# 1_cpu_mmu.net
KiCad netlist of a schematic drawn in EAGLE
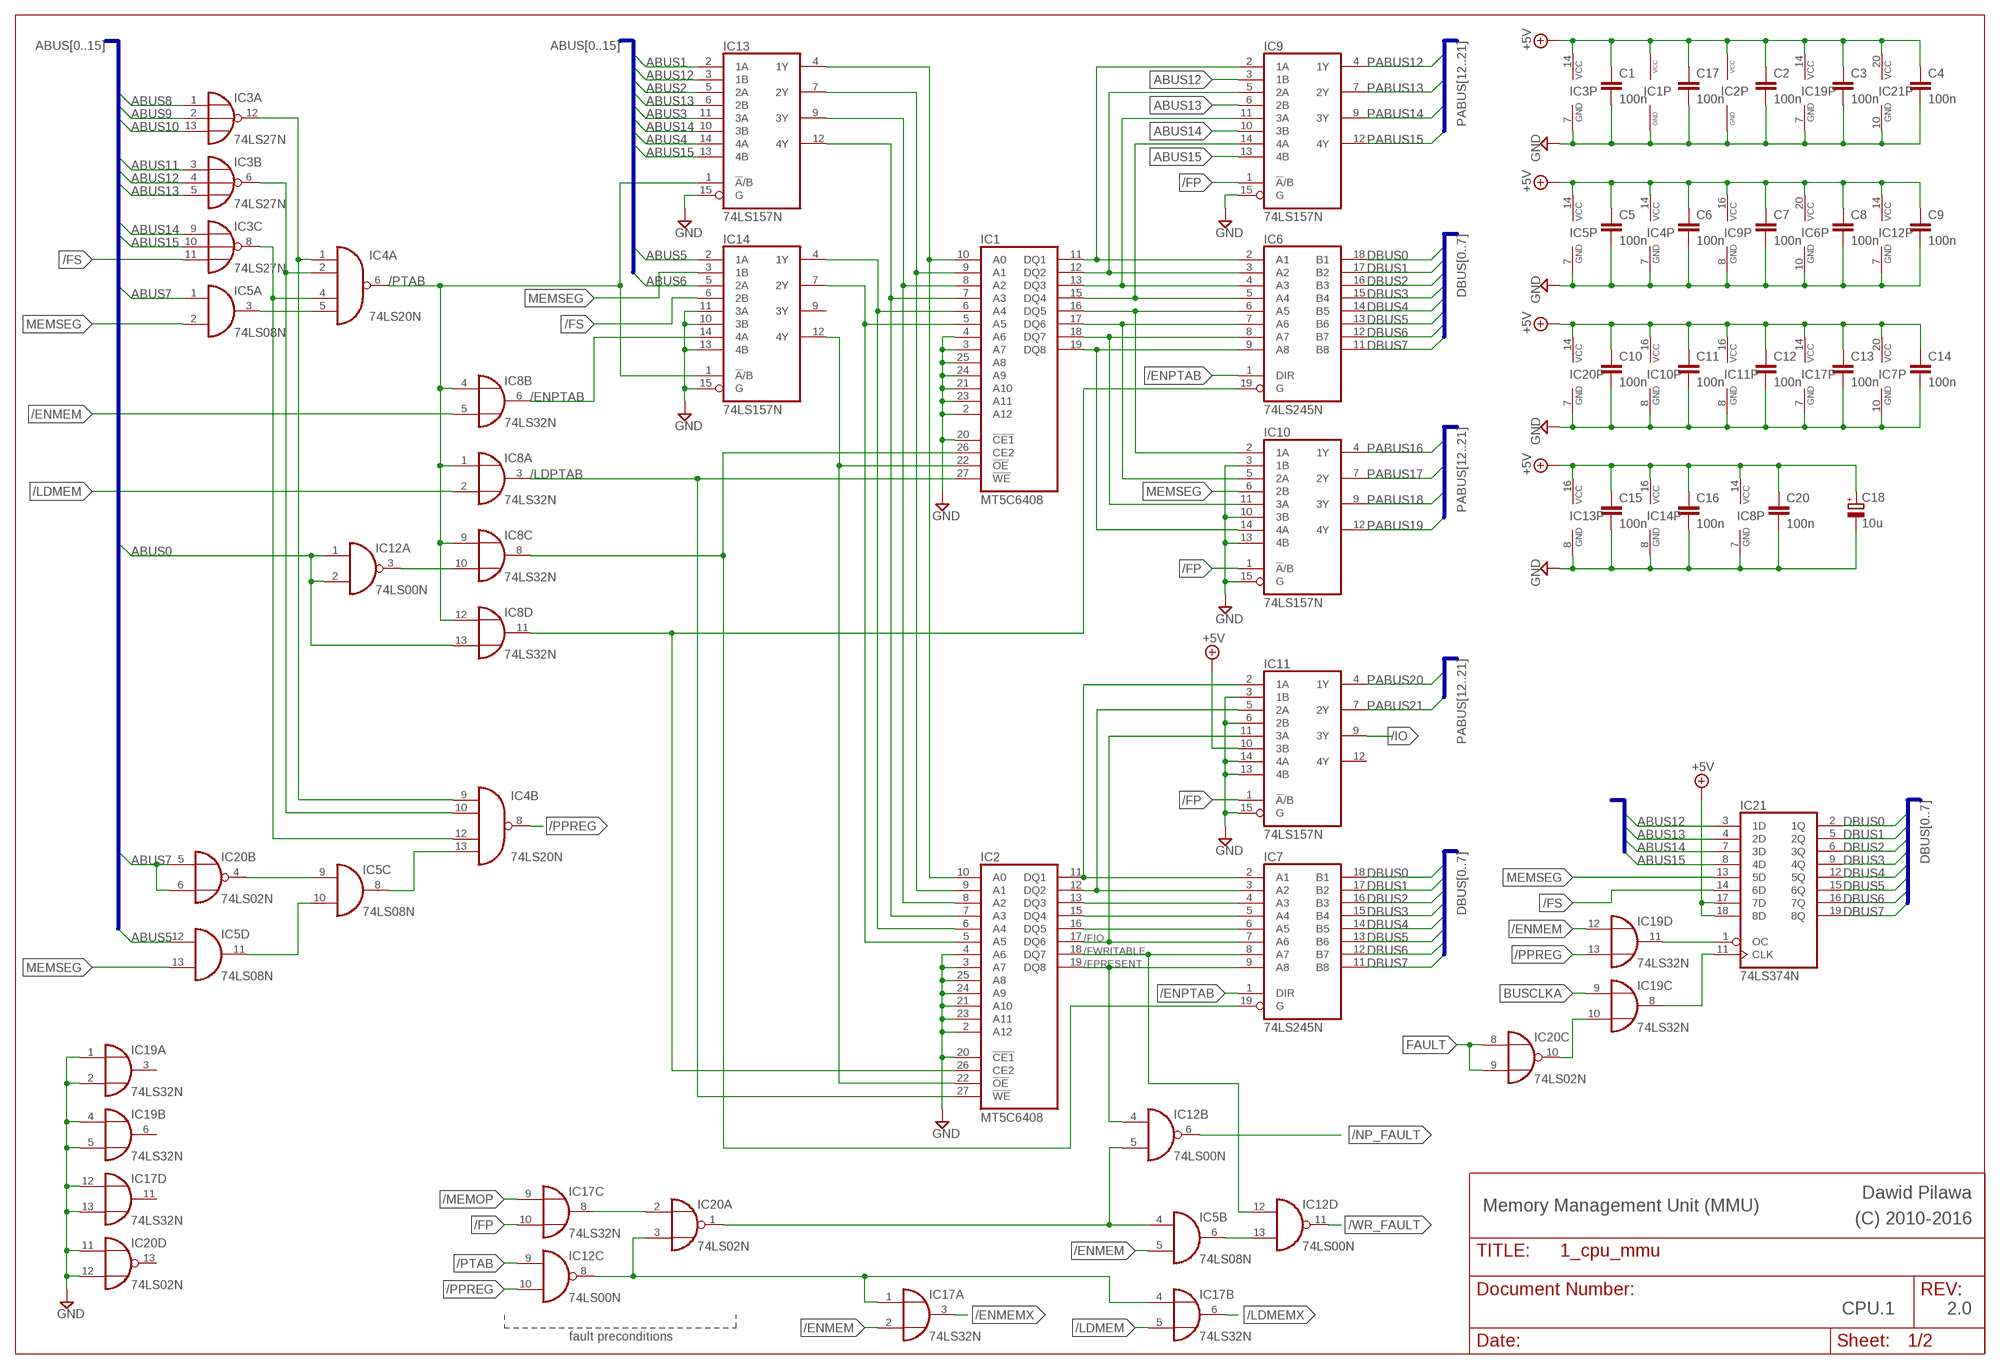
[diagram p0: schematic, sheet 1]
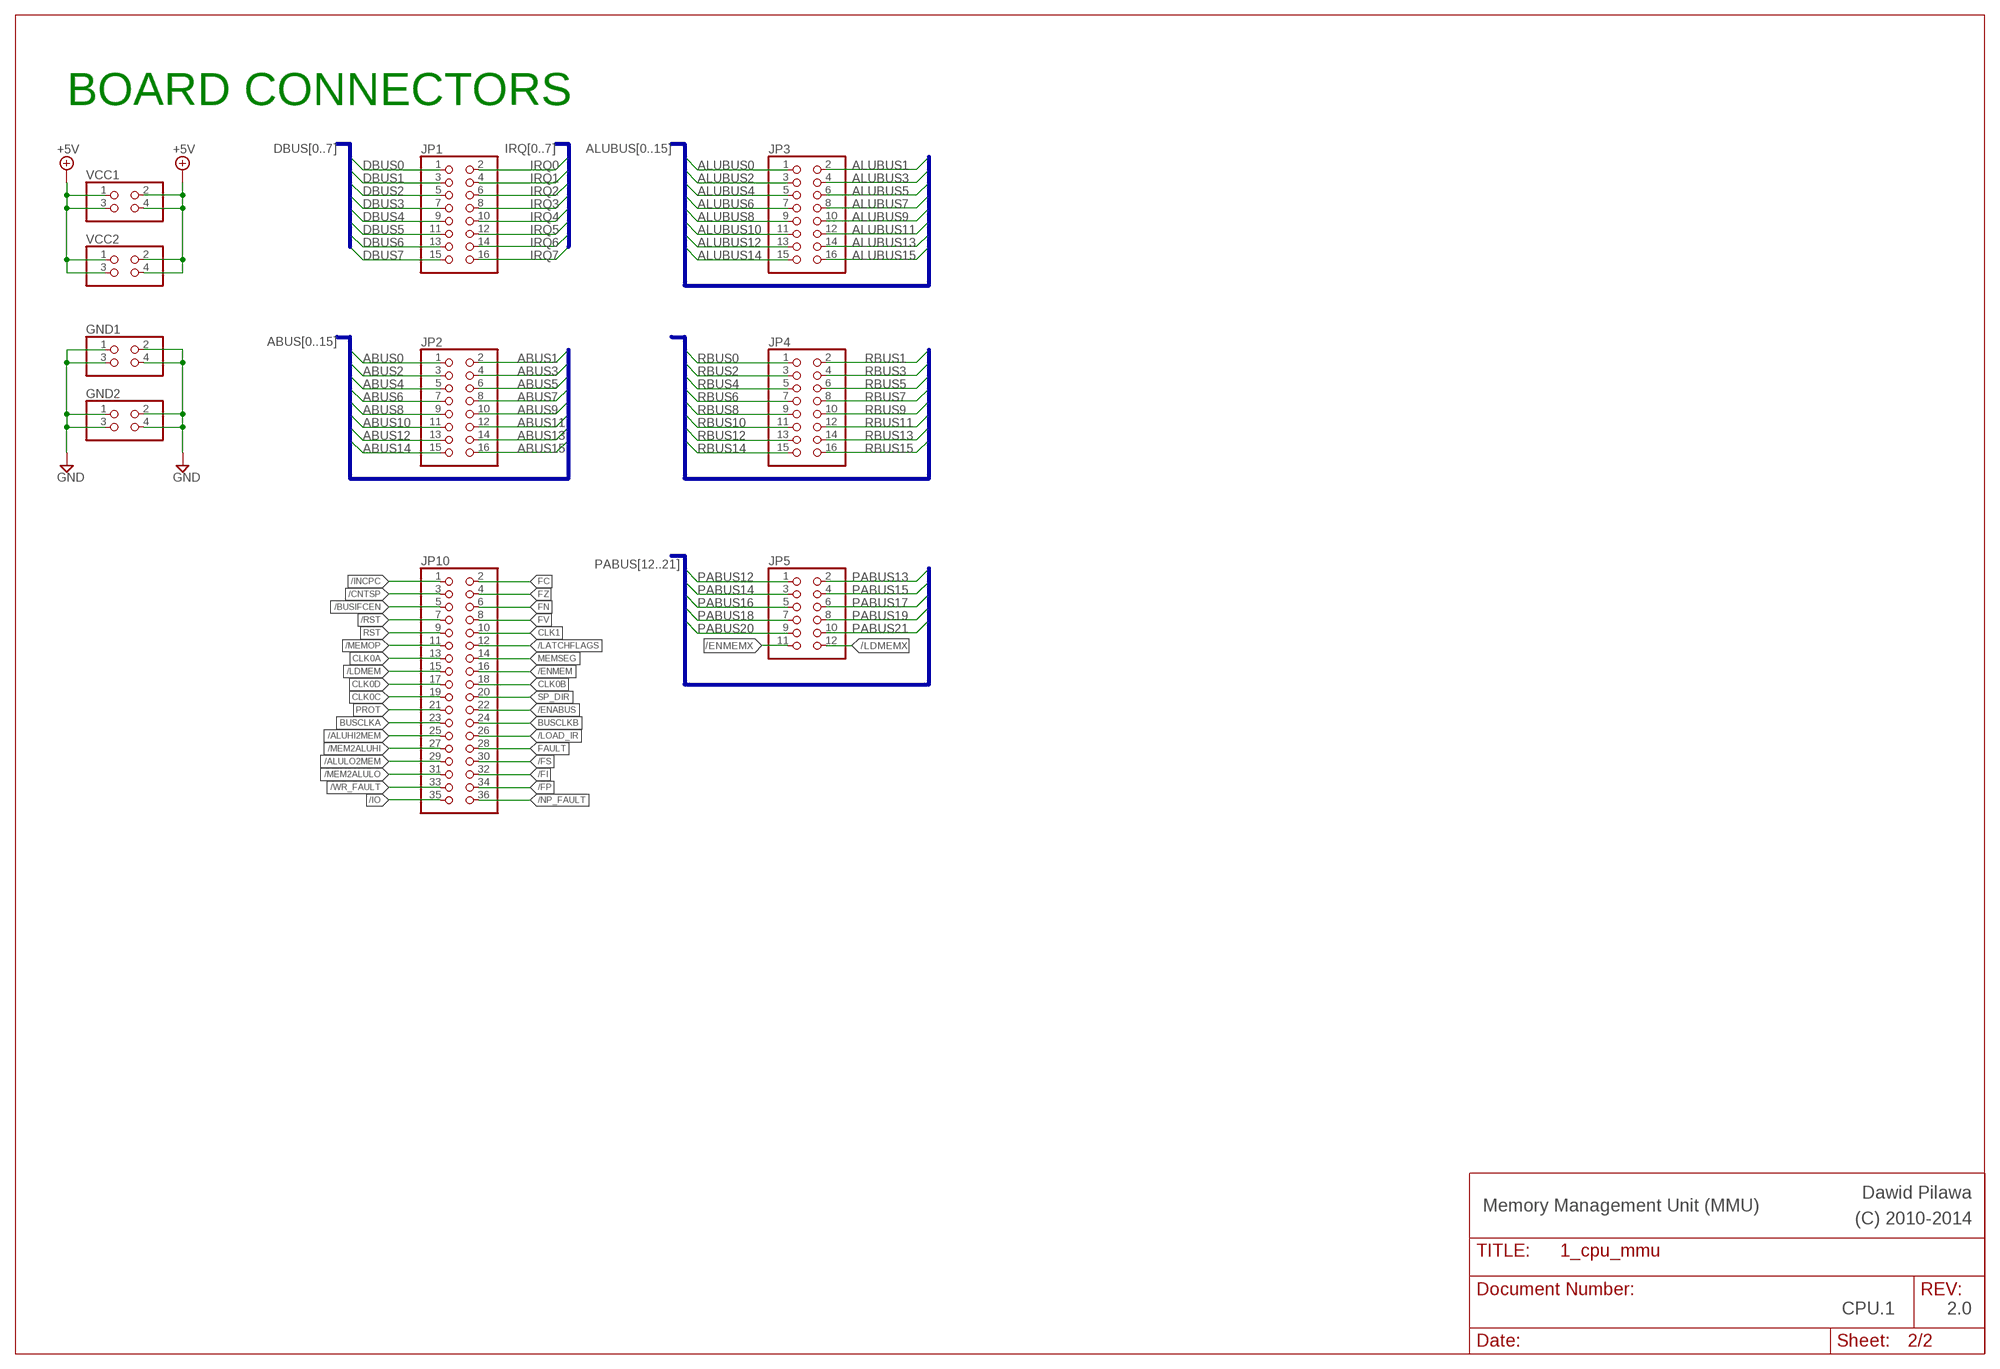
[diagram p1: schematic, sheet 2]

(export (version "E")
  (design (tool "Eeschema 10.0.6"))
  (components
    (comp (ref "C1")
      (value "100n")
      (footprint "eagle-import:C050-024X044")
      (libsource (lib "eagle-import") (part "C-EU050-024X044"))
    )
    (comp (ref "C2")
      (value "100n")
      (footprint "eagle-import:C050-024X044")
      (libsource (lib "eagle-import") (part "C-EU050-024X044"))
    )
    (comp (ref "C3")
      (value "100n")
      (footprint "eagle-import:C050-024X044")
      (libsource (lib "eagle-import") (part "C-EU050-024X044"))
    )
    (comp (ref "C4")
      (value "100n")
      (footprint "eagle-import:C050-024X044")
      (libsource (lib "eagle-import") (part "C-EU050-024X044"))
    )
    (comp (ref "C5")
      (value "100n")
      (footprint "eagle-import:C050-024X044")
      (libsource (lib "eagle-import") (part "C-EU050-024X044"))
    )
    (comp (ref "C6")
      (value "100n")
      (footprint "eagle-import:C050-024X044")
      (libsource (lib "eagle-import") (part "C-EU050-024X044"))
    )
    (comp (ref "C7")
      (value "100n")
      (footprint "eagle-import:C050-024X044")
      (libsource (lib "eagle-import") (part "C-EU050-024X044"))
    )
    (comp (ref "C8")
      (value "100n")
      (footprint "eagle-import:C050-024X044")
      (libsource (lib "eagle-import") (part "C-EU050-024X044"))
    )
    (comp (ref "C9")
      (value "100n")
      (footprint "eagle-import:C050-024X044")
      (libsource (lib "eagle-import") (part "C-EU050-024X044"))
    )
    (comp (ref "C10")
      (value "100n")
      (footprint "eagle-import:C050-024X044")
      (libsource (lib "eagle-import") (part "C-EU050-024X044"))
    )
    (comp (ref "C11")
      (value "100n")
      (footprint "eagle-import:C050-024X044")
      (libsource (lib "eagle-import") (part "C-EU050-024X044"))
    )
    (comp (ref "C12")
      (value "100n")
      (footprint "eagle-import:C050-024X044")
      (libsource (lib "eagle-import") (part "C-EU050-024X044"))
    )
    (comp (ref "C13")
      (value "100n")
      (footprint "eagle-import:C050-024X044")
      (libsource (lib "eagle-import") (part "C-EU050-024X044"))
    )
    (comp (ref "C14")
      (value "100n")
      (footprint "eagle-import:C050-024X044")
      (libsource (lib "eagle-import") (part "C-EU050-024X044"))
    )
    (comp (ref "C15")
      (value "100n")
      (footprint "eagle-import:C050-024X044")
      (libsource (lib "eagle-import") (part "C-EU050-024X044"))
    )
    (comp (ref "C16")
      (value "100n")
      (footprint "eagle-import:C050-024X044")
      (libsource (lib "eagle-import") (part "C-EU050-024X044"))
    )
    (comp (ref "C17")
      (value "100n")
      (footprint "eagle-import:C050-024X044")
      (libsource (lib "eagle-import") (part "C-EU050-024X044"))
    )
    (comp (ref "C18")
      (value "10u")
      (footprint "eagle-import:E2,5-6")
      (libsource (lib "eagle-import") (part "CPOL-EUE2.5-6"))
    )
    (comp (ref "C20")
      (value "100n")
      (footprint "eagle-import:C050-024X044")
      (libsource (lib "eagle-import") (part "C-EU050-024X044"))
    )
    (comp (ref "IC1")
      (value "MT5C6408")
      (footprint "eagle-import:DIL28-3")
      (libsource (lib "eagle-import") (part "MT5C6408"))
    )
    (comp (ref "IC2")
      (value "MT5C6408")
      (footprint "eagle-import:DIL28-3")
      (libsource (lib "eagle-import") (part "MT5C6408"))
    )
    (comp (ref "IC3")
      (value "74LS27N")
      (footprint "eagle-import:DIL14")
      (libsource (lib "eagle-import") (part "7427NLS"))
    )
    (comp (ref "IC4")
      (value "74LS20N")
      (footprint "eagle-import:DIL14")
      (libsource (lib "eagle-import") (part "7420NLS"))
    )
    (comp (ref "IC5")
      (value "74LS08N")
      (footprint "eagle-import:DIL14")
      (libsource (lib "eagle-import") (part "7408NLS"))
    )
    (comp (ref "IC6")
      (value "74LS245N")
      (footprint "eagle-import:DIL20")
      (libsource (lib "eagle-import") (part "74245NLS"))
    )
    (comp (ref "IC7")
      (value "74LS245N")
      (footprint "eagle-import:DIL20")
      (libsource (lib "eagle-import") (part "74245NLS"))
    )
    (comp (ref "IC8")
      (value "74LS32N")
      (footprint "eagle-import:DIL14")
      (libsource (lib "eagle-import") (part "7432NLS"))
    )
    (comp (ref "IC9")
      (value "74LS157N")
      (footprint "eagle-import:DIL16")
      (libsource (lib "eagle-import") (part "74157NLS"))
    )
    (comp (ref "IC10")
      (value "74LS157N")
      (footprint "eagle-import:DIL16")
      (libsource (lib "eagle-import") (part "74157NLS"))
    )
    (comp (ref "IC11")
      (value "74LS157N")
      (footprint "eagle-import:DIL16")
      (libsource (lib "eagle-import") (part "74157NLS"))
    )
    (comp (ref "IC12")
      (value "74LS00N")
      (footprint "eagle-import:DIL14")
      (libsource (lib "eagle-import") (part "7400NLS"))
    )
    (comp (ref "IC13")
      (value "74LS157N")
      (footprint "eagle-import:DIL16")
      (libsource (lib "eagle-import") (part "74157NLS"))
    )
    (comp (ref "IC14")
      (value "74LS157N")
      (footprint "eagle-import:DIL16")
      (libsource (lib "eagle-import") (part "74157NLS"))
    )
    (comp (ref "IC17")
      (value "74LS32N")
      (footprint "eagle-import:DIL14")
      (libsource (lib "eagle-import") (part "7432NLS"))
    )
    (comp (ref "IC19")
      (value "74LS32N")
      (footprint "eagle-import:DIL14")
      (libsource (lib "eagle-import") (part "7432NLS"))
    )
    (comp (ref "IC20")
      (value "74LS02N")
      (footprint "eagle-import:DIL14")
      (libsource (lib "eagle-import") (part "7402NLS"))
    )
    (comp (ref "IC21")
      (value "74LS374N")
      (footprint "eagle-import:DIL20")
      (libsource (lib "eagle-import") (part "74374NLS"))
    )
    (comp (ref "GND1")
      (value "PINHD-2X2")
      (footprint "eagle-import:2X02")
      (libsource (lib "eagle-import") (part "PINHD-2X2"))
    )
    (comp (ref "GND2")
      (value "PINHD-2X2")
      (footprint "eagle-import:2X02")
      (libsource (lib "eagle-import") (part "PINHD-2X2"))
    )
    (comp (ref "JP1")
      (value "PINHD-2X8")
      (footprint "eagle-import:2X08")
      (libsource (lib "eagle-import") (part "PINHD-2X8"))
    )
    (comp (ref "JP2")
      (value "PINHD-2X8")
      (footprint "eagle-import:2X08")
      (libsource (lib "eagle-import") (part "PINHD-2X8"))
    )
    (comp (ref "JP3")
      (value "PINHD-2X8")
      (footprint "eagle-import:2X08")
      (libsource (lib "eagle-import") (part "PINHD-2X8"))
    )
    (comp (ref "JP4")
      (value "PINHD-2X8")
      (footprint "eagle-import:2X08")
      (libsource (lib "eagle-import") (part "PINHD-2X8"))
    )
    (comp (ref "JP5")
      (value "PINHD-2X6")
      (footprint "eagle-import:2X06")
      (libsource (lib "eagle-import") (part "PINHD-2X6"))
    )
    (comp (ref "JP10")
      (value "PINHD-2X18")
      (footprint "eagle-import:2X18")
      (libsource (lib "eagle-import") (part "PINHD-2X18"))
    )
    (comp (ref "VCC1")
      (value "PINHD-2X2")
      (footprint "eagle-import:2X02")
      (libsource (lib "eagle-import") (part "PINHD-2X2"))
    )
    (comp (ref "VCC2")
      (value "PINHD-2X2")
      (footprint "eagle-import:2X02")
      (libsource (lib "eagle-import") (part "PINHD-2X2"))
    )
  )
  (nets
    (net (code "1") (name "+5V") (class "Default")
      (node (ref "C1") (pin "1") (pinfunction "1_1") (pintype "passive"))
      (node (ref "C10") (pin "1") (pinfunction "1_1") (pintype "passive"))
      (node (ref "C11") (pin "1") (pinfunction "1_1") (pintype "passive"))
      (node (ref "C12") (pin "1") (pinfunction "1_1") (pintype "passive"))
      (node (ref "C13") (pin "1") (pinfunction "1_1") (pintype "passive"))
      (node (ref "C14") (pin "1") (pinfunction "1_1") (pintype "passive"))
      (node (ref "C15") (pin "1") (pinfunction "1_1") (pintype "passive"))
      (node (ref "C16") (pin "1") (pinfunction "1_1") (pintype "passive"))
      (node (ref "C17") (pin "1") (pinfunction "1_1") (pintype "passive"))
      (node (ref "C18") (pin "+") (pinfunction "+_+") (pintype "passive"))
      (node (ref "C2") (pin "1") (pinfunction "1_1") (pintype "passive"))
      (node (ref "C20") (pin "1") (pinfunction "1_1") (pintype "passive"))
      (node (ref "C3") (pin "1") (pinfunction "1_1") (pintype "passive"))
      (node (ref "C4") (pin "1") (pinfunction "1_1") (pintype "passive"))
      (node (ref "C5") (pin "1") (pinfunction "1_1") (pintype "passive"))
      (node (ref "C6") (pin "1") (pinfunction "1_1") (pintype "passive"))
      (node (ref "C7") (pin "1") (pinfunction "1_1") (pintype "passive"))
      (node (ref "C8") (pin "1") (pinfunction "1_1") (pintype "passive"))
      (node (ref "C9") (pin "1") (pinfunction "1_1") (pintype "passive"))
      (node (ref "IC1") (pin "28") (pinfunction "VCC_28") (pintype "power_in"))
      (node (ref "IC10") (pin "16") (pinfunction "VCC_16") (pintype "power_in"))
      (node (ref "IC11") (pin "10") (pinfunction "3B_10") (pintype "input"))
      (node (ref "IC11") (pin "16") (pinfunction "VCC_16") (pintype "power_in"))
      (node (ref "IC12") (pin "14") (pinfunction "VCC_14") (pintype "power_in"))
      (node (ref "IC13") (pin "16") (pinfunction "VCC_16") (pintype "power_in"))
      (node (ref "IC14") (pin "16") (pinfunction "VCC_16") (pintype "power_in"))
      (node (ref "IC17") (pin "14") (pinfunction "VCC_14") (pintype "power_in"))
      (node (ref "IC19") (pin "14") (pinfunction "VCC_14") (pintype "power_in"))
      (node (ref "IC2") (pin "28") (pinfunction "VCC_28") (pintype "power_in"))
      (node (ref "IC20") (pin "14") (pinfunction "VCC_14") (pintype "power_in"))
      (node (ref "IC21") (pin "17") (pinfunction "7D_17") (pintype "input"))
      (node (ref "IC21") (pin "18") (pinfunction "8D_18") (pintype "input"))
      (node (ref "IC21") (pin "20") (pinfunction "VCC_20") (pintype "power_in"))
      (node (ref "IC3") (pin "14") (pinfunction "VCC_14") (pintype "power_in"))
      (node (ref "IC4") (pin "14") (pinfunction "VCC_14") (pintype "power_in"))
      (node (ref "IC5") (pin "14") (pinfunction "VCC_14") (pintype "power_in"))
      (node (ref "IC6") (pin "20") (pinfunction "VCC_20") (pintype "power_in"))
      (node (ref "IC7") (pin "20") (pinfunction "VCC_20") (pintype "power_in"))
      (node (ref "IC8") (pin "14") (pinfunction "VCC_14") (pintype "power_in"))
      (node (ref "IC9") (pin "16") (pinfunction "VCC_16") (pintype "power_in"))
      (node (ref "VCC1") (pin "1") (pinfunction "1_1") (pintype "passive"))
      (node (ref "VCC1") (pin "2") (pinfunction "2_2") (pintype "passive"))
      (node (ref "VCC1") (pin "3") (pinfunction "3_3") (pintype "passive"))
      (node (ref "VCC1") (pin "4") (pinfunction "4_4") (pintype "passive"))
      (node (ref "VCC2") (pin "1") (pinfunction "1_1") (pintype "passive"))
      (node (ref "VCC2") (pin "2") (pinfunction "2_2") (pintype "passive"))
      (node (ref "VCC2") (pin "3") (pinfunction "3_3") (pintype "passive"))
      (node (ref "VCC2") (pin "4") (pinfunction "4_4") (pintype "passive"))
    )
    (net (code "10") (name "ABUS0") (class "Default")
      (node (ref "IC12") (pin "1") (pinfunction "I0_1") (pintype "input"))
      (node (ref "IC12") (pin "2") (pinfunction "I1_2") (pintype "input"))
      (node (ref "IC8") (pin "13") (pinfunction "I1_13") (pintype "input"))
      (node (ref "JP2") (pin "1") (pinfunction "1_1") (pintype "passive"))
    )
    (net (code "11") (name "ABUS1") (class "Default")
      (node (ref "IC13") (pin "2") (pinfunction "1A_2") (pintype "input"))
      (node (ref "JP2") (pin "2") (pinfunction "2_2") (pintype "passive"))
    )
    (net (code "12") (name "ABUS2") (class "Default")
      (node (ref "IC13") (pin "5") (pinfunction "2A_5") (pintype "input"))
      (node (ref "JP2") (pin "3") (pinfunction "3_3") (pintype "passive"))
    )
    (net (code "13") (name "ABUS3") (class "Default")
      (node (ref "IC13") (pin "11") (pinfunction "3A_11") (pintype "input"))
      (node (ref "JP2") (pin "4") (pinfunction "4_4") (pintype "passive"))
    )
    (net (code "14") (name "ABUS4") (class "Default")
      (node (ref "IC13") (pin "14") (pinfunction "4A_14") (pintype "input"))
      (node (ref "JP2") (pin "5") (pinfunction "5_5") (pintype "passive"))
    )
    (net (code "15") (name "ABUS5") (class "Default")
      (node (ref "IC14") (pin "2") (pinfunction "1A_2") (pintype "input"))
      (node (ref "IC5") (pin "12") (pinfunction "I0_12") (pintype "input"))
      (node (ref "JP2") (pin "6") (pinfunction "6_6") (pintype "passive"))
    )
    (net (code "16") (name "ABUS6") (class "Default")
      (node (ref "IC14") (pin "5") (pinfunction "2A_5") (pintype "input"))
      (node (ref "JP2") (pin "7") (pinfunction "7_7") (pintype "passive"))
    )
    (net (code "17") (name "ABUS7") (class "Default")
      (node (ref "IC20") (pin "5") (pinfunction "I0_5") (pintype "input"))
      (node (ref "IC20") (pin "6") (pinfunction "I1_6") (pintype "input"))
      (node (ref "IC5") (pin "1") (pinfunction "I0_1") (pintype "input"))
      (node (ref "JP2") (pin "8") (pinfunction "8_8") (pintype "passive"))
    )
    (net (code "18") (name "ABUS8") (class "Default")
      (node (ref "IC3") (pin "1") (pinfunction "I0_1") (pintype "input"))
      (node (ref "JP2") (pin "9") (pinfunction "9_9") (pintype "passive"))
    )
    (net (code "19") (name "ABUS9") (class "Default")
      (node (ref "IC3") (pin "2") (pinfunction "I1_2") (pintype "input"))
      (node (ref "JP2") (pin "10") (pinfunction "10_10") (pintype "passive"))
    )
    (net (code "20") (name "ABUS10") (class "Default")
      (node (ref "IC3") (pin "13") (pinfunction "I2_13") (pintype "input"))
      (node (ref "JP2") (pin "11") (pinfunction "11_11") (pintype "passive"))
    )
    (net (code "21") (name "ABUS11") (class "Default")
      (node (ref "IC3") (pin "3") (pinfunction "I0_3") (pintype "input"))
      (node (ref "JP2") (pin "12") (pinfunction "12_12") (pintype "passive"))
    )
    (net (code "22") (name "ABUS12") (class "Default")
      (node (ref "IC13") (pin "3") (pinfunction "1B_3") (pintype "input"))
      (node (ref "IC21") (pin "3") (pinfunction "1D_3") (pintype "input"))
      (node (ref "IC3") (pin "4") (pinfunction "I1_4") (pintype "input"))
      (node (ref "IC9") (pin "3") (pinfunction "1B_3") (pintype "input"))
      (node (ref "JP2") (pin "13") (pinfunction "13_13") (pintype "passive"))
    )
    (net (code "23") (name "ABUS13") (class "Default")
      (node (ref "IC13") (pin "6") (pinfunction "2B_6") (pintype "input"))
      (node (ref "IC21") (pin "4") (pinfunction "2D_4") (pintype "input"))
      (node (ref "IC3") (pin "5") (pinfunction "I2_5") (pintype "input"))
      (node (ref "IC9") (pin "6") (pinfunction "2B_6") (pintype "input"))
      (node (ref "JP2") (pin "14") (pinfunction "14_14") (pintype "passive"))
    )
    (net (code "24") (name "ABUS14") (class "Default")
      (node (ref "IC13") (pin "10") (pinfunction "3B_10") (pintype "input"))
      (node (ref "IC21") (pin "7") (pinfunction "3D_7") (pintype "input"))
      (node (ref "IC3") (pin "9") (pinfunction "I0_9") (pintype "input"))
      (node (ref "IC9") (pin "10") (pinfunction "3B_10") (pintype "input"))
      (node (ref "JP2") (pin "15") (pinfunction "15_15") (pintype "passive"))
    )
    (net (code "25") (name "ABUS15") (class "Default")
      (node (ref "IC13") (pin "13") (pinfunction "4B_13") (pintype "input"))
      (node (ref "IC21") (pin "8") (pinfunction "4D_8") (pintype "input"))
      (node (ref "IC3") (pin "10") (pinfunction "I1_10") (pintype "input"))
      (node (ref "IC9") (pin "13") (pinfunction "4B_13") (pintype "input"))
      (node (ref "JP2") (pin "16") (pinfunction "16_16") (pintype "passive"))
    )
    (net (code "26") (name "ALUBUS0") (class "Default")
      (node (ref "JP3") (pin "1") (pinfunction "1_1") (pintype "passive"))
    )
    (net (code "27") (name "ALUBUS1") (class "Default")
      (node (ref "JP3") (pin "2") (pinfunction "2_2") (pintype "passive"))
    )
    (net (code "28") (name "ALUBUS2") (class "Default")
      (node (ref "JP3") (pin "3") (pinfunction "3_3") (pintype "passive"))
    )
    (net (code "29") (name "ALUBUS3") (class "Default")
      (node (ref "JP3") (pin "4") (pinfunction "4_4") (pintype "passive"))
    )
    (net (code "30") (name "ALUBUS4") (class "Default")
      (node (ref "JP3") (pin "5") (pinfunction "5_5") (pintype "passive"))
    )
    (net (code "31") (name "ALUBUS5") (class "Default")
      (node (ref "JP3") (pin "6") (pinfunction "6_6") (pintype "passive"))
    )
    (net (code "32") (name "ALUBUS6") (class "Default")
      (node (ref "JP3") (pin "7") (pinfunction "7_7") (pintype "passive"))
    )
    (net (code "33") (name "ALUBUS7") (class "Default")
      (node (ref "JP3") (pin "8") (pinfunction "8_8") (pintype "passive"))
    )
    (net (code "34") (name "ALUBUS8") (class "Default")
      (node (ref "JP3") (pin "9") (pinfunction "9_9") (pintype "passive"))
    )
    (net (code "35") (name "ALUBUS9") (class "Default")
      (node (ref "JP3") (pin "10") (pinfunction "10_10") (pintype "passive"))
    )
    (net (code "36") (name "ALUBUS10") (class "Default")
      (node (ref "JP3") (pin "11") (pinfunction "11_11") (pintype "passive"))
    )
    (net (code "37") (name "ALUBUS11") (class "Default")
      (node (ref "JP3") (pin "12") (pinfunction "12_12") (pintype "passive"))
    )
    (net (code "38") (name "ALUBUS12") (class "Default")
      (node (ref "JP3") (pin "13") (pinfunction "13_13") (pintype "passive"))
    )
    (net (code "39") (name "ALUBUS13") (class "Default")
      (node (ref "JP3") (pin "14") (pinfunction "14_14") (pintype "passive"))
    )
    (net (code "40") (name "ALUBUS14") (class "Default")
      (node (ref "JP3") (pin "15") (pinfunction "15_15") (pintype "passive"))
    )
    (net (code "41") (name "ALUBUS15") (class "Default")
      (node (ref "JP3") (pin "16") (pinfunction "16_16") (pintype "passive"))
    )
    (net (code "42") (name "BUSCLKA") (class "Default")
      (node (ref "IC19") (pin "9") (pinfunction "I0_9") (pintype "input"))
      (node (ref "JP10") (pin "23") (pinfunction "23_23") (pintype "passive"))
    )
    (net (code "43") (name "BUSCLKB") (class "Default")
      (node (ref "JP10") (pin "24") (pinfunction "24_24") (pintype "passive"))
    )
    (net (code "44") (name "CLK0A") (class "Default")
      (node (ref "JP10") (pin "13") (pinfunction "13_13") (pintype "passive"))
    )
    (net (code "45") (name "CLK0B") (class "Default")
      (node (ref "JP10") (pin "18") (pinfunction "18_18") (pintype "passive"))
    )
    (net (code "46") (name "CLK0C") (class "Default")
      (node (ref "JP10") (pin "19") (pinfunction "19_19") (pintype "passive"))
    )
    (net (code "47") (name "CLK0D") (class "Default")
      (node (ref "JP10") (pin "17") (pinfunction "17_17") (pintype "passive"))
    )
    (net (code "48") (name "CLK1") (class "Default")
      (node (ref "JP10") (pin "10") (pinfunction "10_10") (pintype "passive"))
    )
    (net (code "49") (name "DBUS0") (class "Default")
      (node (ref "IC21") (pin "2") (pinfunction "1Q_2") (pintype "tri_state"))
      (node (ref "IC6") (pin "18") (pinfunction "B1_18") (pintype "bidirectional"))
      (node (ref "IC7") (pin "18") (pinfunction "B1_18") (pintype "bidirectional"))
      (node (ref "JP1") (pin "1") (pinfunction "1_1") (pintype "passive"))
    )
    (net (code "50") (name "DBUS1") (class "Default")
      (node (ref "IC21") (pin "5") (pinfunction "2Q_5") (pintype "tri_state"))
      (node (ref "IC6") (pin "17") (pinfunction "B2_17") (pintype "bidirectional"))
      (node (ref "IC7") (pin "17") (pinfunction "B2_17") (pintype "bidirectional"))
      (node (ref "JP1") (pin "3") (pinfunction "3_3") (pintype "passive"))
    )
    (net (code "51") (name "DBUS2") (class "Default")
      (node (ref "IC21") (pin "6") (pinfunction "3Q_6") (pintype "tri_state"))
      (node (ref "IC6") (pin "16") (pinfunction "B3_16") (pintype "bidirectional"))
      (node (ref "IC7") (pin "16") (pinfunction "B3_16") (pintype "bidirectional"))
      (node (ref "JP1") (pin "5") (pinfunction "5_5") (pintype "passive"))
    )
    (net (code "52") (name "DBUS3") (class "Default")
      (node (ref "IC21") (pin "9") (pinfunction "4Q_9") (pintype "tri_state"))
      (node (ref "IC6") (pin "15") (pinfunction "B4_15") (pintype "bidirectional"))
      (node (ref "IC7") (pin "15") (pinfunction "B4_15") (pintype "bidirectional"))
      (node (ref "JP1") (pin "7") (pinfunction "7_7") (pintype "passive"))
    )
    (net (code "53") (name "DBUS4") (class "Default")
      (node (ref "IC21") (pin "12") (pinfunction "5Q_12") (pintype "tri_state"))
      (node (ref "IC6") (pin "14") (pinfunction "B5_14") (pintype "bidirectional"))
      (node (ref "IC7") (pin "14") (pinfunction "B5_14") (pintype "bidirectional"))
      (node (ref "JP1") (pin "9") (pinfunction "9_9") (pintype "passive"))
    )
    (net (code "54") (name "DBUS5") (class "Default")
      (node (ref "IC21") (pin "15") (pinfunction "6Q_15") (pintype "tri_state"))
      (node (ref "IC6") (pin "13") (pinfunction "B6_13") (pintype "bidirectional"))
      (node (ref "IC7") (pin "13") (pinfunction "B6_13") (pintype "bidirectional"))
      (node (ref "JP1") (pin "11") (pinfunction "11_11") (pintype "passive"))
    )
    (net (code "55") (name "DBUS6") (class "Default")
      (node (ref "IC21") (pin "16") (pinfunction "7Q_16") (pintype "tri_state"))
      (node (ref "IC6") (pin "12") (pinfunction "B7_12") (pintype "bidirectional"))
      (node (ref "IC7") (pin "12") (pinfunction "B7_12") (pintype "bidirectional"))
      (node (ref "JP1") (pin "13") (pinfunction "13_13") (pintype "passive"))
    )
    (net (code "56") (name "DBUS7") (class "Default")
      (node (ref "IC21") (pin "19") (pinfunction "8Q_19") (pintype "tri_state"))
      (node (ref "IC6") (pin "11") (pinfunction "B8_11") (pintype "bidirectional"))
      (node (ref "IC7") (pin "11") (pinfunction "B8_11") (pintype "bidirectional"))
      (node (ref "JP1") (pin "15") (pinfunction "15_15") (pintype "passive"))
    )
    (net (code "57") (name "FAULT") (class "Default")
      (node (ref "IC20") (pin "8") (pinfunction "I0_8") (pintype "input"))
      (node (ref "IC20") (pin "9") (pinfunction "I1_9") (pintype "input"))
      (node (ref "JP10") (pin "28") (pinfunction "28_28") (pintype "passive"))
    )
    (net (code "58") (name "FC") (class "Default")
      (node (ref "JP10") (pin "2") (pinfunction "2_2") (pintype "passive"))
    )
    (net (code "59") (name "FN") (class "Default")
      (node (ref "JP10") (pin "6") (pinfunction "6_6") (pintype "passive"))
    )
    (net (code "60") (name "FV") (class "Default")
      (node (ref "JP10") (pin "8") (pinfunction "8_8") (pintype "passive"))
    )
    (net (code "61") (name "FZ") (class "Default")
      (node (ref "JP10") (pin "4") (pinfunction "4_4") (pintype "passive"))
    )
    (net (code "62") (name "GND") (class "Default")
      (node (ref "C1") (pin "2") (pinfunction "2_2") (pintype "passive"))
      (node (ref "C10") (pin "2") (pinfunction "2_2") (pintype "passive"))
      (node (ref "C11") (pin "2") (pinfunction "2_2") (pintype "passive"))
      (node (ref "C12") (pin "2") (pinfunction "2_2") (pintype "passive"))
      (node (ref "C13") (pin "2") (pinfunction "2_2") (pintype "passive"))
      (node (ref "C14") (pin "2") (pinfunction "2_2") (pintype "passive"))
      (node (ref "C15") (pin "2") (pinfunction "2_2") (pintype "passive"))
      (node (ref "C16") (pin "2") (pinfunction "2_2") (pintype "passive"))
      (node (ref "C17") (pin "2") (pinfunction "2_2") (pintype "passive"))
      (node (ref "C18") (pin "-") (pinfunction "-_-") (pintype "passive"))
      (node (ref "C2") (pin "2") (pinfunction "2_2") (pintype "passive"))
      (node (ref "C20") (pin "2") (pinfunction "2_2") (pintype "passive"))
      (node (ref "C3") (pin "2") (pinfunction "2_2") (pintype "passive"))
      (node (ref "C4") (pin "2") (pinfunction "2_2") (pintype "passive"))
      (node (ref "C5") (pin "2") (pinfunction "2_2") (pintype "passive"))
      (node (ref "C6") (pin "2") (pinfunction "2_2") (pintype "passive"))
      (node (ref "C7") (pin "2") (pinfunction "2_2") (pintype "passive"))
      (node (ref "C8") (pin "2") (pinfunction "2_2") (pintype "passive"))
      (node (ref "C9") (pin "2") (pinfunction "2_2") (pintype "passive"))
      (node (ref "GND1") (pin "1") (pinfunction "1_1") (pintype "passive"))
      (node (ref "GND1") (pin "2") (pinfunction "2_2") (pintype "passive"))
      (node (ref "GND1") (pin "3") (pinfunction "3_3") (pintype "passive"))
      (node (ref "GND1") (pin "4") (pinfunction "4_4") (pintype "passive"))
      (node (ref "GND2") (pin "1") (pinfunction "1_1") (pintype "passive"))
      (node (ref "GND2") (pin "2") (pinfunction "2_2") (pintype "passive"))
      (node (ref "GND2") (pin "3") (pinfunction "3_3") (pintype "passive"))
      (node (ref "GND2") (pin "4") (pinfunction "4_4") (pintype "passive"))
      (node (ref "IC1") (pin "14") (pinfunction "GND_14") (pintype "power_in"))
      (node (ref "IC1") (pin "2") (pinfunction "A12_2") (pintype "input"))
      (node (ref "IC1") (pin "20") (pinfunction "~{CE1}_20") (pintype "input"))
      (node (ref "IC1") (pin "21") (pinfunction "A10_21") (pintype "input"))
      (node (ref "IC1") (pin "23") (pinfunction "A11_23") (pintype "input"))
      (node (ref "IC1") (pin "24") (pinfunction "A9_24") (pintype "input"))
      (node (ref "IC1") (pin "25") (pinfunction "A8_25") (pintype "input"))
      (node (ref "IC1") (pin "3") (pinfunction "A7_3") (pintype "input"))
      (node (ref "IC1") (pin "4") (pinfunction "A6_4") (pintype "input"))
      (node (ref "IC10") (pin "10") (pinfunction "3B_10") (pintype "input"))
      (node (ref "IC10") (pin "13") (pinfunction "4B_13") (pintype "input"))
      (node (ref "IC10") (pin "15") (pinfunction "G_15") (pintype "input"))
      (node (ref "IC10") (pin "3") (pinfunction "1B_3") (pintype "input"))
      (node (ref "IC10") (pin "8") (pinfunction "GND_8") (pintype "power_in"))
      (node (ref "IC11") (pin "13") (pinfunction "4B_13") (pintype "input"))
      (node (ref "IC11") (pin "14") (pinfunction "4A_14") (pintype "input"))
      (node (ref "IC11") (pin "15") (pinfunction "G_15") (pintype "input"))
      (node (ref "IC11") (pin "3") (pinfunction "1B_3") (pintype "input"))
      (node (ref "IC11") (pin "6") (pinfunction "2B_6") (pintype "input"))
      (node (ref "IC11") (pin "8") (pinfunction "GND_8") (pintype "power_in"))
      (node (ref "IC12") (pin "7") (pinfunction "GND_7") (pintype "power_in"))
      (node (ref "IC13") (pin "15") (pinfunction "G_15") (pintype "input"))
      (node (ref "IC13") (pin "8") (pinfunction "GND_8") (pintype "power_in"))
      (node (ref "IC14") (pin "10") (pinfunction "3B_10") (pintype "input"))
      (node (ref "IC14") (pin "11") (pinfunction "3A_11") (pintype "input"))
      (node (ref "IC14") (pin "13") (pinfunction "4B_13") (pintype "input"))
      (node (ref "IC14") (pin "15") (pinfunction "G_15") (pintype "input"))
      (node (ref "IC14") (pin "8") (pinfunction "GND_8") (pintype "power_in"))
      (node (ref "IC17") (pin "12") (pinfunction "I0_12") (pintype "input"))
      (node (ref "IC17") (pin "13") (pinfunction "I1_13") (pintype "input"))
      (node (ref "IC17") (pin "7") (pinfunction "GND_7") (pintype "power_in"))
      (node (ref "IC19") (pin "1") (pinfunction "I0_1") (pintype "input"))
      (node (ref "IC19") (pin "2") (pinfunction "I1_2") (pintype "input"))
      (node (ref "IC19") (pin "4") (pinfunction "I0_4") (pintype "input"))
      (node (ref "IC19") (pin "5") (pinfunction "I1_5") (pintype "input"))
      (node (ref "IC19") (pin "7") (pinfunction "GND_7") (pintype "power_in"))
      (node (ref "IC2") (pin "14") (pinfunction "GND_14") (pintype "power_in"))
      (node (ref "IC2") (pin "2") (pinfunction "A12_2") (pintype "input"))
      (node (ref "IC2") (pin "20") (pinfunction "~{CE1}_20") (pintype "input"))
      (node (ref "IC2") (pin "21") (pinfunction "A10_21") (pintype "input"))
      (node (ref "IC2") (pin "23") (pinfunction "A11_23") (pintype "input"))
      (node (ref "IC2") (pin "24") (pinfunction "A9_24") (pintype "input"))
      (node (ref "IC2") (pin "25") (pinfunction "A8_25") (pintype "input"))
      (node (ref "IC2") (pin "3") (pinfunction "A7_3") (pintype "input"))
      (node (ref "IC2") (pin "4") (pinfunction "A6_4") (pintype "input"))
      (node (ref "IC20") (pin "11") (pinfunction "I0_11") (pintype "input"))
      (node (ref "IC20") (pin "12") (pinfunction "I1_12") (pintype "input"))
      (node (ref "IC20") (pin "7") (pinfunction "GND_7") (pintype "power_in"))
      (node (ref "IC21") (pin "10") (pinfunction "GND_10") (pintype "power_in"))
      (node (ref "IC3") (pin "7") (pinfunction "GND_7") (pintype "power_in"))
      (node (ref "IC4") (pin "7") (pinfunction "GND_7") (pintype "power_in"))
      (node (ref "IC5") (pin "7") (pinfunction "GND_7") (pintype "power_in"))
      (node (ref "IC6") (pin "10") (pinfunction "GND_10") (pintype "power_in"))
      (node (ref "IC7") (pin "10") (pinfunction "GND_10") (pintype "power_in"))
      (node (ref "IC8") (pin "7") (pinfunction "GND_7") (pintype "power_in"))
      (node (ref "IC9") (pin "15") (pinfunction "G_15") (pintype "input"))
      (node (ref "IC9") (pin "8") (pinfunction "GND_8") (pintype "power_in"))
    )
    (net (code "63") (name "IRQ0") (class "Default")
      (node (ref "JP1") (pin "2") (pinfunction "2_2") (pintype "passive"))
    )
    (net (code "64") (name "IRQ1") (class "Default")
      (node (ref "JP1") (pin "4") (pinfunction "4_4") (pintype "passive"))
    )
    (net (code "65") (name "IRQ2") (class "Default")
      (node (ref "JP1") (pin "6") (pinfunction "6_6") (pintype "passive"))
    )
    (net (code "66") (name "IRQ3") (class "Default")
      (node (ref "JP1") (pin "8") (pinfunction "8_8") (pintype "passive"))
    )
    (net (code "67") (name "IRQ4") (class "Default")
      (node (ref "JP1") (pin "10") (pinfunction "10_10") (pintype "passive"))
    )
    (net (code "68") (name "IRQ5") (class "Default")
      (node (ref "JP1") (pin "12") (pinfunction "12_12") (pintype "passive"))
    )
    (net (code "69") (name "IRQ6") (class "Default")
      (node (ref "JP1") (pin "14") (pinfunction "14_14") (pintype "passive"))
    )
    (net (code "70") (name "IRQ7") (class "Default")
      (node (ref "JP1") (pin "16") (pinfunction "16_16") (pintype "passive"))
    )
    (net (code "71") (name "MEMSEG") (class "Default")
      (node (ref "IC10") (pin "6") (pinfunction "2B_6") (pintype "input"))
      (node (ref "IC14") (pin "3") (pinfunction "1B_3") (pintype "input"))
      (node (ref "IC21") (pin "13") (pinfunction "5D_13") (pintype "input"))
      (node (ref "IC5") (pin "13") (pinfunction "I1_13") (pintype "input"))
      (node (ref "IC5") (pin "2") (pinfunction "I1_2") (pintype "input"))
      (node (ref "JP10") (pin "14") (pinfunction "14_14") (pintype "passive"))
    )
    (net (code "72") (name "Net-(IC1A-CE2)") (class "Default")
      (node (ref "IC1") (pin "26") (pinfunction "CE2_26") (pintype "input"))
      (node (ref "IC7") (pin "19") (pinfunction "G_19") (pintype "input"))
      (node (ref "IC8") (pin "8") (pinfunction "O_8") (pintype "output"))
    )
    (net (code "73") (name "Net-(IC1A-DQ1)") (class "Default")
      (node (ref "IC1") (pin "11") (pinfunction "DQ1_11") (pintype "bidirectional"))
      (node (ref "IC6") (pin "2") (pinfunction "A1_2") (pintype "bidirectional"))
      (node (ref "IC9") (pin "2") (pinfunction "1A_2") (pintype "input"))
    )
    (net (code "74") (name "Net-(IC1A-DQ2)") (class "Default")
      (node (ref "IC1") (pin "12") (pinfunction "DQ2_12") (pintype "bidirectional"))
      (node (ref "IC6") (pin "3") (pinfunction "A2_3") (pintype "bidirectional"))
      (node (ref "IC9") (pin "5") (pinfunction "2A_5") (pintype "input"))
    )
    (net (code "75") (name "Net-(IC1A-DQ3)") (class "Default")
      (node (ref "IC1") (pin "13") (pinfunction "DQ3_13") (pintype "bidirectional"))
      (node (ref "IC6") (pin "4") (pinfunction "A3_4") (pintype "bidirectional"))
      (node (ref "IC9") (pin "11") (pinfunction "3A_11") (pintype "input"))
    )
    (net (code "76") (name "Net-(IC1A-DQ4)") (class "Default")
      (node (ref "IC1") (pin "15") (pinfunction "DQ4_15") (pintype "bidirectional"))
      (node (ref "IC6") (pin "5") (pinfunction "A4_5") (pintype "bidirectional"))
      (node (ref "IC9") (pin "14") (pinfunction "4A_14") (pintype "input"))
    )
    (net (code "77") (name "Net-(IC2A-CE2)") (class "Default")
      (node (ref "IC2") (pin "26") (pinfunction "CE2_26") (pintype "input"))
      (node (ref "IC6") (pin "19") (pinfunction "G_19") (pintype "input"))
      (node (ref "IC8") (pin "11") (pinfunction "O_11") (pintype "output"))
    )
    (net (code "78") (name "Net-(IC2A-DQ3)") (class "Default")
      (node (ref "IC2") (pin "13") (pinfunction "DQ3_13") (pintype "bidirectional"))
      (node (ref "IC7") (pin "4") (pinfunction "A3_4") (pintype "bidirectional"))
    )
    (net (code "79") (name "Net-(IC2A-DQ4)") (class "Default")
      (node (ref "IC2") (pin "15") (pinfunction "DQ4_15") (pintype "bidirectional"))
      (node (ref "IC7") (pin "5") (pinfunction "A4_5") (pintype "bidirectional"))
    )
    (net (code "80") (name "Net-(IC2A-DQ5)") (class "Default")
      (node (ref "IC2") (pin "16") (pinfunction "DQ5_16") (pintype "bidirectional"))
      (node (ref "IC7") (pin "6") (pinfunction "A5_6") (pintype "bidirectional"))
    )
    (net (code "81") (name "Net-(IC3A-O)") (class "Default")
      (node (ref "IC3") (pin "12") (pinfunction "O_12") (pintype "output"))
      (node (ref "IC4") (pin "1") (pinfunction "I0_1") (pintype "input"))
      (node (ref "IC4") (pin "9") (pinfunction "I0_9") (pintype "input"))
    )
    (net (code "82") (name "Net-(IC3B-O)") (class "Default")
      (node (ref "IC3") (pin "6") (pinfunction "O_6") (pintype "output"))
      (node (ref "IC4") (pin "10") (pinfunction "I1_10") (pintype "input"))
      (node (ref "IC4") (pin "2") (pinfunction "I1_2") (pintype "input"))
    )
    (net (code "83") (name "Net-(IC3C-O)") (class "Default")
      (node (ref "IC3") (pin "8") (pinfunction "O_8") (pintype "output"))
      (node (ref "IC4") (pin "12") (pinfunction "I2_12") (pintype "input"))
      (node (ref "IC4") (pin "4") (pinfunction "I2_4") (pintype "input"))
    )
    (net (code "84") (name "Net-(IC4A-I3)") (class "Default")
      (node (ref "IC4") (pin "5") (pinfunction "I3_5") (pintype "input"))
      (node (ref "IC5") (pin "3") (pinfunction "O_3") (pintype "output"))
    )
    (net (code "85") (name "Net-(IC4B-I3)") (class "Default")
      (node (ref "IC4") (pin "13") (pinfunction "I3_13") (pintype "input"))
      (node (ref "IC5") (pin "8") (pinfunction "O_8") (pintype "output"))
    )
    (net (code "86") (name "Net-(IC5C-I1)") (class "Default")
      (node (ref "IC5") (pin "10") (pinfunction "I1_10") (pintype "input"))
      (node (ref "IC5") (pin "11") (pinfunction "O_11") (pintype "output"))
    )
    (net (code "87") (name "Net-(IC10A-1A)") (class "Default")
      (node (ref "IC1") (pin "16") (pinfunction "DQ5_16") (pintype "bidirectional"))
      (node (ref "IC10") (pin "2") (pinfunction "1A_2") (pintype "input"))
      (node (ref "IC6") (pin "6") (pinfunction "A5_6") (pintype "bidirectional"))
    )
    (net (code "88") (name "Net-(IC10A-2A)") (class "Default")
      (node (ref "IC1") (pin "17") (pinfunction "DQ6_17") (pintype "bidirectional"))
      (node (ref "IC10") (pin "5") (pinfunction "2A_5") (pintype "input"))
      (node (ref "IC6") (pin "7") (pinfunction "A6_7") (pintype "bidirectional"))
    )
    (net (code "89") (name "Net-(IC10A-3A)") (class "Default")
      (node (ref "IC1") (pin "18") (pinfunction "DQ7_18") (pintype "bidirectional"))
      (node (ref "IC10") (pin "11") (pinfunction "3A_11") (pintype "input"))
      (node (ref "IC6") (pin "8") (pinfunction "A7_8") (pintype "bidirectional"))
    )
    (net (code "90") (name "Net-(IC10A-4A)") (class "Default")
      (node (ref "IC1") (pin "19") (pinfunction "DQ8_19") (pintype "bidirectional"))
      (node (ref "IC10") (pin "14") (pinfunction "4A_14") (pintype "input"))
      (node (ref "IC6") (pin "9") (pinfunction "A8_9") (pintype "bidirectional"))
    )
    (net (code "91") (name "Net-(IC11A-1A)") (class "Default")
      (node (ref "IC11") (pin "2") (pinfunction "1A_2") (pintype "input"))
      (node (ref "IC2") (pin "11") (pinfunction "DQ1_11") (pintype "bidirectional"))
      (node (ref "IC7") (pin "2") (pinfunction "A1_2") (pintype "bidirectional"))
    )
    (net (code "92") (name "Net-(IC11A-2A)") (class "Default")
      (node (ref "IC11") (pin "5") (pinfunction "2A_5") (pintype "input"))
      (node (ref "IC2") (pin "12") (pinfunction "DQ2_12") (pintype "bidirectional"))
      (node (ref "IC7") (pin "3") (pinfunction "A2_3") (pintype "bidirectional"))
    )
    (net (code "93") (name "Net-(IC12A-O)") (class "Default")
      (node (ref "IC12") (pin "3") (pinfunction "O_3") (pintype "output"))
      (node (ref "IC8") (pin "10") (pinfunction "I1_10") (pintype "input"))
    )
    (net (code "94") (name "Net-(IC12B-I1)") (class "Default")
      (node (ref "IC12") (pin "5") (pinfunction "I1_5") (pintype "input"))
      (node (ref "IC20") (pin "1") (pinfunction "O_1") (pintype "output"))
      (node (ref "IC5") (pin "4") (pinfunction "I0_4") (pintype "input"))
    )
    (net (code "95") (name "Net-(IC12C-O)") (class "Default")
      (node (ref "IC12") (pin "8") (pinfunction "O_8") (pintype "output"))
      (node (ref "IC17") (pin "1") (pinfunction "I0_1") (pintype "input"))
      (node (ref "IC17") (pin "4") (pinfunction "I0_4") (pintype "input"))
      (node (ref "IC20") (pin "3") (pinfunction "I1_3") (pintype "input"))
    )
    (net (code "96") (name "Net-(IC12D-I1)") (class "Default")
      (node (ref "IC12") (pin "13") (pinfunction "I1_13") (pintype "input"))
      (node (ref "IC5") (pin "6") (pinfunction "O_6") (pintype "output"))
    )
    (net (code "97") (name "Net-(IC13A-1Y)") (class "Default")
      (node (ref "IC1") (pin "10") (pinfunction "A0_10") (pintype "input"))
      (node (ref "IC13") (pin "4") (pinfunction "1Y_4") (pintype "output"))
      (node (ref "IC2") (pin "10") (pinfunction "A0_10") (pintype "input"))
    )
    (net (code "98") (name "Net-(IC13A-2Y)") (class "Default")
      (node (ref "IC1") (pin "9") (pinfunction "A1_9") (pintype "input"))
      (node (ref "IC13") (pin "7") (pinfunction "2Y_7") (pintype "output"))
      (node (ref "IC2") (pin "9") (pinfunction "A1_9") (pintype "input"))
    )
    (net (code "99") (name "Net-(IC13A-3Y)") (class "Default")
      (node (ref "IC1") (pin "8") (pinfunction "A2_8") (pintype "input"))
      (node (ref "IC13") (pin "9") (pinfunction "3Y_9") (pintype "output"))
      (node (ref "IC2") (pin "8") (pinfunction "A2_8") (pintype "input"))
    )
    (net (code "100") (name "Net-(IC13A-4Y)") (class "Default")
      (node (ref "IC1") (pin "7") (pinfunction "A3_7") (pintype "input"))
      (node (ref "IC13") (pin "12") (pinfunction "4Y_12") (pintype "output"))
      (node (ref "IC2") (pin "7") (pinfunction "A3_7") (pintype "input"))
    )
    (net (code "101") (name "Net-(IC14A-1Y)") (class "Default")
      (node (ref "IC1") (pin "6") (pinfunction "A4_6") (pintype "input"))
      (node (ref "IC14") (pin "4") (pinfunction "1Y_4") (pintype "output"))
      (node (ref "IC2") (pin "6") (pinfunction "A4_6") (pintype "input"))
    )
    (net (code "102") (name "Net-(IC14A-2Y)") (class "Default")
      (node (ref "IC1") (pin "5") (pinfunction "A5_5") (pintype "input"))
      (node (ref "IC14") (pin "7") (pinfunction "2Y_7") (pintype "output"))
      (node (ref "IC2") (pin "5") (pinfunction "A5_5") (pintype "input"))
    )
    (net (code "103") (name "Net-(IC14A-4Y)") (class "Default")
      (node (ref "IC1") (pin "22") (pinfunction "~{OE}_22") (pintype "input"))
      (node (ref "IC14") (pin "12") (pinfunction "4Y_12") (pintype "output"))
      (node (ref "IC2") (pin "22") (pinfunction "~{OE}_22") (pintype "input"))
    )
    (net (code "104") (name "Net-(IC17C-O)") (class "Default")
      (node (ref "IC17") (pin "8") (pinfunction "O_8") (pintype "output"))
      (node (ref "IC20") (pin "2") (pinfunction "I0_2") (pintype "input"))
    )
    (net (code "105") (name "Net-(IC19C-I1)") (class "Default")
      (node (ref "IC19") (pin "10") (pinfunction "I1_10") (pintype "input"))
      (node (ref "IC20") (pin "10") (pinfunction "O_10") (pintype "output"))
    )
    (net (code "106") (name "Net-(IC19C-O)") (class "Default")
      (node (ref "IC19") (pin "8") (pinfunction "O_8") (pintype "output"))
      (node (ref "IC21") (pin "11") (pinfunction "CLK_11") (pintype "input"))
    )
    (net (code "107") (name "Net-(IC19D-O)") (class "Default")
      (node (ref "IC19") (pin "11") (pinfunction "O_11") (pintype "output"))
      (node (ref "IC21") (pin "1") (pinfunction "OC_1") (pintype "input"))
    )
    (net (code "108") (name "Net-(IC20B-O)") (class "Default")
      (node (ref "IC20") (pin "4") (pinfunction "O_4") (pintype "output"))
      (node (ref "IC5") (pin "9") (pinfunction "I0_9") (pintype "input"))
    )
    (net (code "109") (name "PABUS12") (class "Default")
      (node (ref "IC9") (pin "4") (pinfunction "1Y_4") (pintype "output"))
      (node (ref "JP5") (pin "1") (pinfunction "1_1") (pintype "passive"))
    )
    (net (code "110") (name "PABUS13") (class "Default")
      (node (ref "IC9") (pin "7") (pinfunction "2Y_7") (pintype "output"))
      (node (ref "JP5") (pin "2") (pinfunction "2_2") (pintype "passive"))
    )
    (net (code "111") (name "PABUS14") (class "Default")
      (node (ref "IC9") (pin "9") (pinfunction "3Y_9") (pintype "output"))
      (node (ref "JP5") (pin "3") (pinfunction "3_3") (pintype "passive"))
    )
    (net (code "112") (name "PABUS15") (class "Default")
      (node (ref "IC9") (pin "12") (pinfunction "4Y_12") (pintype "output"))
      (node (ref "JP5") (pin "4") (pinfunction "4_4") (pintype "passive"))
    )
    (net (code "113") (name "PABUS16") (class "Default")
      (node (ref "IC10") (pin "4") (pinfunction "1Y_4") (pintype "output"))
      (node (ref "JP5") (pin "5") (pinfunction "5_5") (pintype "passive"))
    )
    (net (code "114") (name "PABUS17") (class "Default")
      (node (ref "IC10") (pin "7") (pinfunction "2Y_7") (pintype "output"))
      (node (ref "JP5") (pin "6") (pinfunction "6_6") (pintype "passive"))
    )
    (net (code "115") (name "PABUS18") (class "Default")
      (node (ref "IC10") (pin "9") (pinfunction "3Y_9") (pintype "output"))
      (node (ref "JP5") (pin "7") (pinfunction "7_7") (pintype "passive"))
    )
    (net (code "116") (name "PABUS19") (class "Default")
      (node (ref "IC10") (pin "12") (pinfunction "4Y_12") (pintype "output"))
      (node (ref "JP5") (pin "8") (pinfunction "8_8") (pintype "passive"))
    )
    (net (code "117") (name "PABUS20") (class "Default")
      (node (ref "IC11") (pin "4") (pinfunction "1Y_4") (pintype "output"))
      (node (ref "JP5") (pin "9") (pinfunction "9_9") (pintype "passive"))
    )
    (net (code "118") (name "PABUS21") (class "Default")
      (node (ref "IC11") (pin "7") (pinfunction "2Y_7") (pintype "output"))
      (node (ref "JP5") (pin "10") (pinfunction "10_10") (pintype "passive"))
    )
    (net (code "119") (name "PROT") (class "Default")
      (node (ref "JP10") (pin "21") (pinfunction "21_21") (pintype "passive"))
    )
    (net (code "120") (name "RBUS0") (class "Default")
      (node (ref "JP4") (pin "1") (pinfunction "1_1") (pintype "passive"))
    )
    (net (code "121") (name "RBUS1") (class "Default")
      (node (ref "JP4") (pin "2") (pinfunction "2_2") (pintype "passive"))
    )
    (net (code "122") (name "RBUS2") (class "Default")
      (node (ref "JP4") (pin "3") (pinfunction "3_3") (pintype "passive"))
    )
    (net (code "123") (name "RBUS3") (class "Default")
      (node (ref "JP4") (pin "4") (pinfunction "4_4") (pintype "passive"))
    )
    (net (code "124") (name "RBUS4") (class "Default")
      (node (ref "JP4") (pin "5") (pinfunction "5_5") (pintype "passive"))
    )
    (net (code "125") (name "RBUS5") (class "Default")
      (node (ref "JP4") (pin "6") (pinfunction "6_6") (pintype "passive"))
    )
    (net (code "126") (name "RBUS6") (class "Default")
      (node (ref "JP4") (pin "7") (pinfunction "7_7") (pintype "passive"))
    )
    (net (code "127") (name "RBUS7") (class "Default")
      (node (ref "JP4") (pin "8") (pinfunction "8_8") (pintype "passive"))
    )
    (net (code "128") (name "RBUS8") (class "Default")
      (node (ref "JP4") (pin "9") (pinfunction "9_9") (pintype "passive"))
    )
    (net (code "129") (name "RBUS9") (class "Default")
      (node (ref "JP4") (pin "10") (pinfunction "10_10") (pintype "passive"))
    )
    (net (code "130") (name "RBUS10") (class "Default")
      (node (ref "JP4") (pin "11") (pinfunction "11_11") (pintype "passive"))
    )
    (net (code "131") (name "RBUS11") (class "Default")
      (node (ref "JP4") (pin "12") (pinfunction "12_12") (pintype "passive"))
    )
    (net (code "132") (name "RBUS12") (class "Default")
      (node (ref "JP4") (pin "13") (pinfunction "13_13") (pintype "passive"))
    )
    (net (code "133") (name "RBUS13") (class "Default")
      (node (ref "JP4") (pin "14") (pinfunction "14_14") (pintype "passive"))
    )
    (net (code "134") (name "RBUS14") (class "Default")
      (node (ref "JP4") (pin "15") (pinfunction "15_15") (pintype "passive"))
    )
    (net (code "135") (name "RBUS15") (class "Default")
      (node (ref "JP4") (pin "16") (pinfunction "16_16") (pintype "passive"))
    )
    (net (code "136") (name "RST") (class "Default")
      (node (ref "JP10") (pin "9") (pinfunction "9_9") (pintype "passive"))
    )
    (net (code "137") (name "SP_DIR") (class "Default")
      (node (ref "JP10") (pin "20") (pinfunction "20_20") (pintype "passive"))
    )
    (net (code "138") (name "unconnected-(IC11A-4Y-Pad12)") (class "Default")
      (node (ref "IC11") (pin "12") (pinfunction "4Y_12") (pintype "output"))
    )
    (net (code "139") (name "unconnected-(IC14A-3Y-Pad9)") (class "Default")
      (node (ref "IC14") (pin "9") (pinfunction "3Y_9") (pintype "output"))
    )
    (net (code "140") (name "unconnected-(IC17D-O-Pad11)") (class "Default")
      (node (ref "IC17") (pin "11") (pinfunction "O_11") (pintype "output"))
    )
    (net (code "141") (name "unconnected-(IC19A-O-Pad3)") (class "Default")
      (node (ref "IC19") (pin "3") (pinfunction "O_3") (pintype "output"))
    )
    (net (code "142") (name "unconnected-(IC19B-O-Pad6)") (class "Default")
      (node (ref "IC19") (pin "6") (pinfunction "O_6") (pintype "output"))
    )
    (net (code "143") (name "unconnected-(IC20D-O-Pad13)") (class "Default")
      (node (ref "IC20") (pin "13") (pinfunction "O_13") (pintype "output"))
    )
    (net (code "144") (name "{slash}ALUHI2MEM") (class "Default")
      (node (ref "JP10") (pin "25") (pinfunction "25_25") (pintype "passive"))
    )
    (net (code "145") (name "{slash}ALULO2MEM") (class "Default")
      (node (ref "JP10") (pin "29") (pinfunction "29_29") (pintype "passive"))
    )
    (net (code "146") (name "{slash}BUSIFCEN") (class "Default")
      (node (ref "JP10") (pin "5") (pinfunction "5_5") (pintype "passive"))
    )
    (net (code "147") (name "{slash}CNTSP") (class "Default")
      (node (ref "JP10") (pin "3") (pinfunction "3_3") (pintype "passive"))
    )
    (net (code "148") (name "{slash}ENABUS") (class "Default")
      (node (ref "JP10") (pin "22") (pinfunction "22_22") (pintype "passive"))
    )
    (net (code "149") (name "{slash}ENMEM") (class "Default")
      (node (ref "IC17") (pin "2") (pinfunction "I1_2") (pintype "input"))
      (node (ref "IC19") (pin "12") (pinfunction "I0_12") (pintype "input"))
      (node (ref "IC5") (pin "5") (pinfunction "I1_5") (pintype "input"))
      (node (ref "IC8") (pin "5") (pinfunction "I1_5") (pintype "input"))
      (node (ref "JP10") (pin "16") (pinfunction "16_16") (pintype "passive"))
    )
    (net (code "150") (name "{slash}ENMEMX") (class "Default")
      (node (ref "IC17") (pin "3") (pinfunction "O_3") (pintype "output"))
      (node (ref "JP5") (pin "11") (pinfunction "11_11") (pintype "passive"))
    )
    (net (code "151") (name "{slash}ENPTAB") (class "Default")
      (node (ref "IC14") (pin "14") (pinfunction "4A_14") (pintype "input"))
      (node (ref "IC6") (pin "1") (pinfunction "DIR_1") (pintype "input"))
      (node (ref "IC7") (pin "1") (pinfunction "DIR_1") (pintype "input"))
      (node (ref "IC8") (pin "6") (pinfunction "O_6") (pintype "output"))
    )
    (net (code "152") (name "{slash}FI") (class "Default")
      (node (ref "JP10") (pin "32") (pinfunction "32_32") (pintype "passive"))
    )
    (net (code "153") (name "{slash}FIO") (class "Default")
      (node (ref "IC11") (pin "11") (pinfunction "3A_11") (pintype "input"))
      (node (ref "IC2") (pin "17") (pinfunction "DQ6_17") (pintype "bidirectional"))
      (node (ref "IC7") (pin "7") (pinfunction "A6_7") (pintype "bidirectional"))
    )
    (net (code "154") (name "{slash}FP") (class "Default")
      (node (ref "IC10") (pin "1") (pinfunction "~{A}/B_1") (pintype "input"))
      (node (ref "IC11") (pin "1") (pinfunction "~{A}/B_1") (pintype "input"))
      (node (ref "IC17") (pin "10") (pinfunction "I1_10") (pintype "input"))
      (node (ref "IC9") (pin "1") (pinfunction "~{A}/B_1") (pintype "input"))
      (node (ref "JP10") (pin "34") (pinfunction "34_34") (pintype "passive"))
    )
    (net (code "155") (name "{slash}FPRESENT") (class "Default")
      (node (ref "IC12") (pin "4") (pinfunction "I0_4") (pintype "input"))
      (node (ref "IC2") (pin "19") (pinfunction "DQ8_19") (pintype "bidirectional"))
      (node (ref "IC7") (pin "9") (pinfunction "A8_9") (pintype "bidirectional"))
    )
    (net (code "156") (name "{slash}FS") (class "Default")
      (node (ref "IC14") (pin "6") (pinfunction "2B_6") (pintype "input"))
      (node (ref "IC21") (pin "14") (pinfunction "6D_14") (pintype "input"))
      (node (ref "IC3") (pin "11") (pinfunction "I2_11") (pintype "input"))
      (node (ref "JP10") (pin "30") (pinfunction "30_30") (pintype "passive"))
    )
    (net (code "157") (name "{slash}FWRITABLE") (class "Default")
      (node (ref "IC12") (pin "12") (pinfunction "I0_12") (pintype "input"))
      (node (ref "IC2") (pin "18") (pinfunction "DQ7_18") (pintype "bidirectional"))
      (node (ref "IC7") (pin "8") (pinfunction "A7_8") (pintype "bidirectional"))
    )
    (net (code "158") (name "{slash}INCPC") (class "Default")
      (node (ref "JP10") (pin "1") (pinfunction "1_1") (pintype "passive"))
    )
    (net (code "159") (name "{slash}IO") (class "Default")
      (node (ref "IC11") (pin "9") (pinfunction "3Y_9") (pintype "output"))
      (node (ref "JP10") (pin "35") (pinfunction "35_35") (pintype "passive"))
    )
    (net (code "160") (name "{slash}LATCHFLAGS") (class "Default")
      (node (ref "JP10") (pin "12") (pinfunction "12_12") (pintype "passive"))
    )
    (net (code "161") (name "{slash}LDMEM") (class "Default")
      (node (ref "IC17") (pin "5") (pinfunction "I1_5") (pintype "input"))
      (node (ref "IC8") (pin "2") (pinfunction "I1_2") (pintype "input"))
      (node (ref "JP10") (pin "15") (pinfunction "15_15") (pintype "passive"))
    )
    (net (code "162") (name "{slash}LDMEMX") (class "Default")
      (node (ref "IC17") (pin "6") (pinfunction "O_6") (pintype "output"))
      (node (ref "JP5") (pin "12") (pinfunction "12_12") (pintype "passive"))
    )
    (net (code "163") (name "{slash}LDPTAB") (class "Default")
      (node (ref "IC1") (pin "27") (pinfunction "~{WE}_27") (pintype "input"))
      (node (ref "IC2") (pin "27") (pinfunction "~{WE}_27") (pintype "input"))
      (node (ref "IC8") (pin "3") (pinfunction "O_3") (pintype "output"))
    )
    (net (code "164") (name "{slash}LOAD_IR") (class "Default")
      (node (ref "JP10") (pin "26") (pinfunction "26_26") (pintype "passive"))
    )
    (net (code "165") (name "{slash}MEM2ALUHI") (class "Default")
      (node (ref "JP10") (pin "27") (pinfunction "27_27") (pintype "passive"))
    )
    (net (code "166") (name "{slash}MEM2ALULO") (class "Default")
      (node (ref "JP10") (pin "31") (pinfunction "31_31") (pintype "passive"))
    )
    (net (code "167") (name "{slash}MEMOP") (class "Default")
      (node (ref "IC17") (pin "9") (pinfunction "I0_9") (pintype "input"))
      (node (ref "JP10") (pin "11") (pinfunction "11_11") (pintype "passive"))
    )
    (net (code "168") (name "{slash}NP_FAULT") (class "Default")
      (node (ref "IC12") (pin "6") (pinfunction "O_6") (pintype "output"))
      (node (ref "JP10") (pin "36") (pinfunction "36_36") (pintype "passive"))
    )
    (net (code "169") (name "{slash}PPREG") (class "Default")
      (node (ref "IC12") (pin "10") (pinfunction "I1_10") (pintype "input"))
      (node (ref "IC19") (pin "13") (pinfunction "I1_13") (pintype "input"))
      (node (ref "IC4") (pin "8") (pinfunction "O_8") (pintype "output"))
    )
    (net (code "170") (name "{slash}PTAB") (class "Default")
      (node (ref "IC12") (pin "9") (pinfunction "I0_9") (pintype "input"))
      (node (ref "IC13") (pin "1") (pinfunction "~{A}/B_1") (pintype "input"))
      (node (ref "IC14") (pin "1") (pinfunction "~{A}/B_1") (pintype "input"))
      (node (ref "IC4") (pin "6") (pinfunction "O_6") (pintype "output"))
      (node (ref "IC8") (pin "1") (pinfunction "I0_1") (pintype "input"))
      (node (ref "IC8") (pin "12") (pinfunction "I0_12") (pintype "input"))
      (node (ref "IC8") (pin "4") (pinfunction "I0_4") (pintype "input"))
      (node (ref "IC8") (pin "9") (pinfunction "I0_9") (pintype "input"))
    )
    (net (code "171") (name "{slash}RST") (class "Default")
      (node (ref "JP10") (pin "7") (pinfunction "7_7") (pintype "passive"))
    )
    (net (code "172") (name "{slash}WR_FAULT") (class "Default")
      (node (ref "IC12") (pin "11") (pinfunction "O_11") (pintype "output"))
      (node (ref "JP10") (pin "33") (pinfunction "33_33") (pintype "passive"))
    )
  )
)
